# temp_measure.net
KiCad netlist of a schematic drawn in Altium Designer
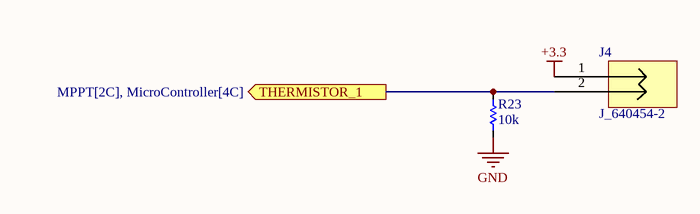
[diagram p0: temp_measure.SchDoc]

(export (version "E")
  (design (tool "Eeschema 10.0.6"))
  (components
    (comp (ref "J4")
      (value "J_640454-2")
      (footprint "640454-2")
      (description "2 Positions Header, Unshrouded Connector 0.100\" (2.54mm) Through Hole Tin")
      (libsource (lib "University of Minnesota - Solar Vehicle Project") (part "Symbol"))
    )
    (comp (ref "R23")
      (value "10k")
      (footprint "0603_RESISTOR")
      (description "RES 10K OHM 1/16W 1% 0603 SMD")
      (fields (field (name "POWER") "62.5mW") (field (name "TOLERANCE") "1%"))
      (libsource (lib "") (part "Symbol_1"))
    )
  )
  (nets
    (net (code "1") (name "+3.3") (class "Default")
      (node (ref "J4") (pin "1") (pinfunction "1_1") (pintype "passive"))
    )
    (net (code "2") (name "/THERMISTOR_1") (class "Default")
      (node (ref "J4") (pin "2") (pinfunction "2_2") (pintype "passive"))
      (node (ref "R23") (pin "2") (pinfunction "2_2") (pintype "passive"))
    )
    (net (code "3") (name "GND") (class "Default")
      (node (ref "R23") (pin "1") (pinfunction "1_1") (pintype "passive"))
    )
  )
)
